# design.net
KiCad netlist of a schematic drawn in EAGLE
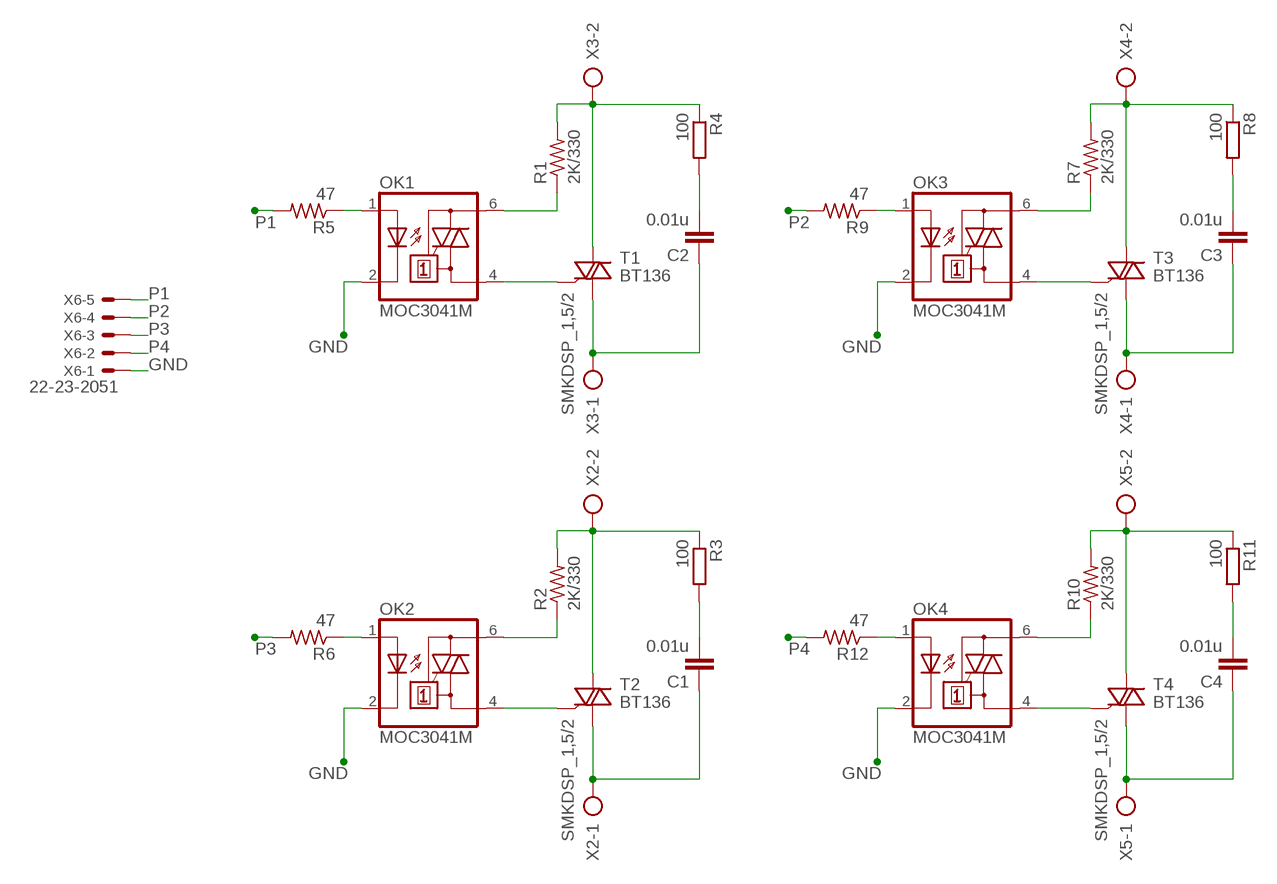
[diagram p0: schematic, sheet 1]

(export (version "E")
  (design (tool "Eeschema 10.0.6"))
  (components
    (comp (ref "C1")
      (value "0.01u")
      (footprint "eagle-import:C050-024X044")
      (libsource (lib "eagle-import") (part "C-EU050-024X044"))
    )
    (comp (ref "C2")
      (value "0.01u")
      (footprint "eagle-import:C050-024X044")
      (libsource (lib "eagle-import") (part "C-EU050-024X044"))
    )
    (comp (ref "C3")
      (value "0.01u")
      (footprint "eagle-import:C050-024X044")
      (libsource (lib "eagle-import") (part "C-EU050-024X044"))
    )
    (comp (ref "C4")
      (value "0.01u")
      (footprint "eagle-import:C050-024X044")
      (libsource (lib "eagle-import") (part "C-EU050-024X044"))
    )
    (comp (ref "OK1")
      (value "MOC3041M")
      (footprint "eagle-import:DIL06")
      (fields (field (name "MF") "FAIRCHILD SEMICONDUCTOR"))
      (libsource (lib "eagle-import") (part "MOC3041M"))
    )
    (comp (ref "OK2")
      (value "MOC3041M")
      (footprint "eagle-import:DIL06")
      (fields (field (name "MF") "FAIRCHILD SEMICONDUCTOR"))
      (libsource (lib "eagle-import") (part "MOC3041M"))
    )
    (comp (ref "OK3")
      (value "MOC3041M")
      (footprint "eagle-import:DIL06")
      (fields (field (name "MF") "FAIRCHILD SEMICONDUCTOR"))
      (libsource (lib "eagle-import") (part "MOC3041M"))
    )
    (comp (ref "OK4")
      (value "MOC3041M")
      (footprint "eagle-import:DIL06")
      (fields (field (name "MF") "FAIRCHILD SEMICONDUCTOR"))
      (libsource (lib "eagle-import") (part "MOC3041M"))
    )
    (comp (ref "R1")
      (value "2K/330")
      (footprint "eagle-import:0204_7")
      (libsource (lib "eagle-import") (part "R-US_0204/7"))
    )
    (comp (ref "R2")
      (value "2K/330")
      (footprint "eagle-import:0204_7")
      (libsource (lib "eagle-import") (part "R-US_0204/7"))
    )
    (comp (ref "R3")
      (value "100")
      (footprint "eagle-import:0204_7")
      (libsource (lib "eagle-import") (part "R-EU_0204/7"))
    )
    (comp (ref "R4")
      (value "100")
      (footprint "eagle-import:0204_7")
      (libsource (lib "eagle-import") (part "R-EU_0204/7"))
    )
    (comp (ref "R5")
      (value "47")
      (footprint "eagle-import:0204_7")
      (libsource (lib "eagle-import") (part "R-US_0204/7"))
    )
    (comp (ref "R6")
      (value "47")
      (footprint "eagle-import:0204_7")
      (libsource (lib "eagle-import") (part "R-US_0204/7"))
    )
    (comp (ref "R7")
      (value "2K/330")
      (footprint "eagle-import:0204_7")
      (libsource (lib "eagle-import") (part "R-US_0204/7"))
    )
    (comp (ref "R8")
      (value "100")
      (footprint "eagle-import:0204_7")
      (libsource (lib "eagle-import") (part "R-EU_0204/7"))
    )
    (comp (ref "R9")
      (value "47")
      (footprint "eagle-import:0204_7")
      (libsource (lib "eagle-import") (part "R-US_0204/7"))
    )
    (comp (ref "R10")
      (value "2K/330")
      (footprint "eagle-import:0204_7")
      (libsource (lib "eagle-import") (part "R-US_0204/7"))
    )
    (comp (ref "R11")
      (value "100")
      (footprint "eagle-import:0204_7")
      (libsource (lib "eagle-import") (part "R-EU_0204/7"))
    )
    (comp (ref "R12")
      (value "47")
      (footprint "eagle-import:0204_7")
      (libsource (lib "eagle-import") (part "R-US_0204/7"))
    )
    (comp (ref "T1")
      (value "BT136")
      (footprint "eagle-import:TO220AB")
      (libsource (lib "eagle-import") (part "BT136"))
    )
    (comp (ref "T2")
      (value "BT136")
      (footprint "eagle-import:TO220AB")
      (libsource (lib "eagle-import") (part "BT136"))
    )
    (comp (ref "T3")
      (value "BT136")
      (footprint "eagle-import:TO220AB")
      (libsource (lib "eagle-import") (part "BT136"))
    )
    (comp (ref "T4")
      (value "BT136")
      (footprint "eagle-import:TO220AB")
      (libsource (lib "eagle-import") (part "BT136"))
    )
    (comp (ref "X2")
      (value "SMKDSP_1,5/2")
      (footprint "eagle-import:SMKDSP_1,5_2")
      (fields (field (name "MF") "FARNELL") (field (name "MPN") "1733570"))
      (libsource (lib "eagle-import") (part "SMKDSP_1,5/2"))
    )
    (comp (ref "X3")
      (value "SMKDSP_1,5/2")
      (footprint "eagle-import:SMKDSP_1,5_2")
      (fields (field (name "MF") "FARNELL") (field (name "MPN") "1733570"))
      (libsource (lib "eagle-import") (part "SMKDSP_1,5/2"))
    )
    (comp (ref "X4")
      (value "SMKDSP_1,5/2")
      (footprint "eagle-import:SMKDSP_1,5_2")
      (fields (field (name "MF") "FARNELL") (field (name "MPN") "1733570"))
      (libsource (lib "eagle-import") (part "SMKDSP_1,5/2"))
    )
    (comp (ref "X5")
      (value "SMKDSP_1,5/2")
      (footprint "eagle-import:SMKDSP_1,5_2")
      (fields (field (name "MF") "FARNELL") (field (name "MPN") "1733570"))
      (libsource (lib "eagle-import") (part "SMKDSP_1,5/2"))
    )
    (comp (ref "X6")
      (value "22-23-2051")
      (footprint "eagle-import:22-23-2051")
      (fields (field (name "MF") "MOLEX"))
      (libsource (lib "eagle-import") (part "22-23-2051"))
    )
  )
  (nets
    (net (code "1") (name "/GND") (class "Default")
      (node (ref "OK1") (pin "2") (pinfunction "C_2") (pintype "passive"))
      (node (ref "OK2") (pin "2") (pinfunction "C_2") (pintype "passive"))
      (node (ref "OK3") (pin "2") (pinfunction "C_2") (pintype "passive"))
      (node (ref "OK4") (pin "2") (pinfunction "C_2") (pintype "passive"))
      (node (ref "X6") (pin "1") (pinfunction "S_1") (pintype "passive"))
    )
    (net (code "2") (name "/P1") (class "Default")
      (node (ref "R5") (pin "2") (pinfunction "2_2") (pintype "passive"))
      (node (ref "X6") (pin "5") (pinfunction "S_5") (pintype "passive"))
    )
    (net (code "3") (name "/P2") (class "Default")
      (node (ref "R9") (pin "2") (pinfunction "2_2") (pintype "passive"))
      (node (ref "X6") (pin "4") (pinfunction "S_4") (pintype "passive"))
    )
    (net (code "4") (name "/P3") (class "Default")
      (node (ref "R6") (pin "2") (pinfunction "2_2") (pintype "passive"))
      (node (ref "X6") (pin "3") (pinfunction "S_3") (pintype "passive"))
    )
    (net (code "5") (name "/P4") (class "Default")
      (node (ref "R12") (pin "2") (pinfunction "2_2") (pintype "passive"))
      (node (ref "X6") (pin "2") (pinfunction "S_2") (pintype "passive"))
    )
    (net (code "6") (name "Net-(C1-Pad2)") (class "Default")
      (node (ref "C1") (pin "2") (pinfunction "2_2") (pintype "passive"))
      (node (ref "R3") (pin "2") (pinfunction "2_2") (pintype "passive"))
    )
    (net (code "7") (name "Net-(C2-Pad2)") (class "Default")
      (node (ref "C2") (pin "2") (pinfunction "2_2") (pintype "passive"))
      (node (ref "R4") (pin "2") (pinfunction "2_2") (pintype "passive"))
    )
    (net (code "8") (name "Net-(C3-Pad2)") (class "Default")
      (node (ref "C3") (pin "2") (pinfunction "2_2") (pintype "passive"))
      (node (ref "R8") (pin "2") (pinfunction "2_2") (pintype "passive"))
    )
    (net (code "9") (name "Net-(C4-Pad2)") (class "Default")
      (node (ref "C4") (pin "2") (pinfunction "2_2") (pintype "passive"))
      (node (ref "R11") (pin "2") (pinfunction "2_2") (pintype "passive"))
    )
    (net (code "10") (name "Net-(OK1-A)") (class "Default")
      (node (ref "OK1") (pin "1") (pinfunction "A_1") (pintype "passive"))
      (node (ref "R5") (pin "1") (pinfunction "1_1") (pintype "passive"))
    )
    (net (code "11") (name "Net-(OK1-A1)") (class "Default")
      (node (ref "OK1") (pin "4") (pinfunction "A1_4") (pintype "passive"))
      (node (ref "T1") (pin "3") (pinfunction "G_3") (pintype "passive"))
    )
    (net (code "12") (name "Net-(OK1-A2)") (class "Default")
      (node (ref "OK1") (pin "6") (pinfunction "A2_6") (pintype "passive"))
      (node (ref "R1") (pin "1") (pinfunction "1_1") (pintype "passive"))
    )
    (net (code "13") (name "Net-(OK2-A)") (class "Default")
      (node (ref "OK2") (pin "1") (pinfunction "A_1") (pintype "passive"))
      (node (ref "R6") (pin "1") (pinfunction "1_1") (pintype "passive"))
    )
    (net (code "14") (name "Net-(OK2-A1)") (class "Default")
      (node (ref "OK2") (pin "4") (pinfunction "A1_4") (pintype "passive"))
      (node (ref "T2") (pin "3") (pinfunction "G_3") (pintype "passive"))
    )
    (net (code "15") (name "Net-(OK2-A2)") (class "Default")
      (node (ref "OK2") (pin "6") (pinfunction "A2_6") (pintype "passive"))
      (node (ref "R2") (pin "1") (pinfunction "1_1") (pintype "passive"))
    )
    (net (code "16") (name "Net-(OK3-A)") (class "Default")
      (node (ref "OK3") (pin "1") (pinfunction "A_1") (pintype "passive"))
      (node (ref "R9") (pin "1") (pinfunction "1_1") (pintype "passive"))
    )
    (net (code "17") (name "Net-(OK3-A1)") (class "Default")
      (node (ref "OK3") (pin "4") (pinfunction "A1_4") (pintype "passive"))
      (node (ref "T3") (pin "3") (pinfunction "G_3") (pintype "passive"))
    )
    (net (code "18") (name "Net-(OK3-A2)") (class "Default")
      (node (ref "OK3") (pin "6") (pinfunction "A2_6") (pintype "passive"))
      (node (ref "R7") (pin "1") (pinfunction "1_1") (pintype "passive"))
    )
    (net (code "19") (name "Net-(OK4-A)") (class "Default")
      (node (ref "OK4") (pin "1") (pinfunction "A_1") (pintype "passive"))
      (node (ref "R12") (pin "1") (pinfunction "1_1") (pintype "passive"))
    )
    (net (code "20") (name "Net-(OK4-A1)") (class "Default")
      (node (ref "OK4") (pin "4") (pinfunction "A1_4") (pintype "passive"))
      (node (ref "T4") (pin "3") (pinfunction "G_3") (pintype "passive"))
    )
    (net (code "21") (name "Net-(OK4-A2)") (class "Default")
      (node (ref "OK4") (pin "6") (pinfunction "A2_6") (pintype "passive"))
      (node (ref "R10") (pin "1") (pinfunction "1_1") (pintype "passive"))
    )
    (net (code "22") (name "Net-(T1-A1)") (class "Default")
      (node (ref "C2") (pin "1") (pinfunction "1_1") (pintype "passive"))
      (node (ref "T1") (pin "1") (pinfunction "A1_1") (pintype "passive"))
      (node (ref "X3") (pin "1") (pinfunction "KL_1") (pintype "passive"))
    )
    (net (code "23") (name "Net-(T1-A2)") (class "Default")
      (node (ref "R1") (pin "2") (pinfunction "2_2") (pintype "passive"))
      (node (ref "R4") (pin "1") (pinfunction "1_1") (pintype "passive"))
      (node (ref "T1") (pin "2") (pinfunction "A2_2") (pintype "passive"))
      (node (ref "X3") (pin "2") (pinfunction "KL_2") (pintype "passive"))
    )
    (net (code "24") (name "Net-(T2-A1)") (class "Default")
      (node (ref "C1") (pin "1") (pinfunction "1_1") (pintype "passive"))
      (node (ref "T2") (pin "1") (pinfunction "A1_1") (pintype "passive"))
      (node (ref "X2") (pin "1") (pinfunction "KL_1") (pintype "passive"))
    )
    (net (code "25") (name "Net-(T2-A2)") (class "Default")
      (node (ref "R2") (pin "2") (pinfunction "2_2") (pintype "passive"))
      (node (ref "R3") (pin "1") (pinfunction "1_1") (pintype "passive"))
      (node (ref "T2") (pin "2") (pinfunction "A2_2") (pintype "passive"))
      (node (ref "X2") (pin "2") (pinfunction "KL_2") (pintype "passive"))
    )
    (net (code "26") (name "Net-(T3-A1)") (class "Default")
      (node (ref "C3") (pin "1") (pinfunction "1_1") (pintype "passive"))
      (node (ref "T3") (pin "1") (pinfunction "A1_1") (pintype "passive"))
      (node (ref "X4") (pin "1") (pinfunction "KL_1") (pintype "passive"))
    )
    (net (code "27") (name "Net-(T3-A2)") (class "Default")
      (node (ref "R7") (pin "2") (pinfunction "2_2") (pintype "passive"))
      (node (ref "R8") (pin "1") (pinfunction "1_1") (pintype "passive"))
      (node (ref "T3") (pin "2") (pinfunction "A2_2") (pintype "passive"))
      (node (ref "X4") (pin "2") (pinfunction "KL_2") (pintype "passive"))
    )
    (net (code "28") (name "Net-(T4-A1)") (class "Default")
      (node (ref "C4") (pin "1") (pinfunction "1_1") (pintype "passive"))
      (node (ref "T4") (pin "1") (pinfunction "A1_1") (pintype "passive"))
      (node (ref "X5") (pin "1") (pinfunction "KL_1") (pintype "passive"))
    )
    (net (code "29") (name "Net-(T4-A2)") (class "Default")
      (node (ref "R10") (pin "2") (pinfunction "2_2") (pintype "passive"))
      (node (ref "R11") (pin "1") (pinfunction "1_1") (pintype "passive"))
      (node (ref "T4") (pin "2") (pinfunction "A2_2") (pintype "passive"))
      (node (ref "X5") (pin "2") (pinfunction "KL_2") (pintype "passive"))
    )
  )
)
